# Reciever_Temp.net
KiCad netlist of a schematic drawn in EAGLE
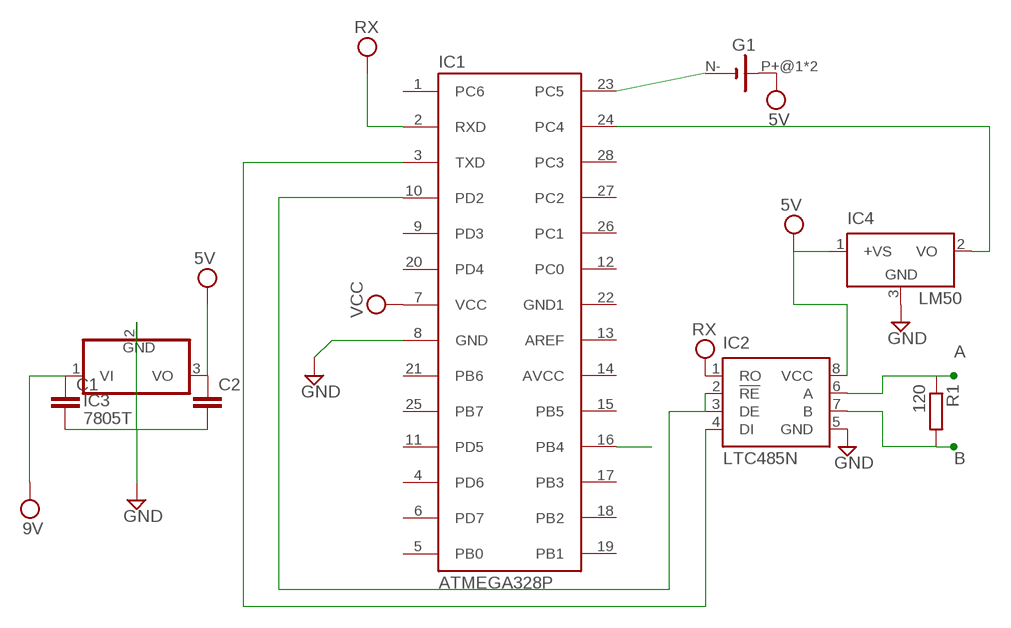
[diagram p0: schematic, sheet 1]

(export (version "E")
  (design (tool "Eeschema 10.0.6"))
  (components
    (comp (ref "C1")
      (value "C-EU050-030X075")
      (footprint "eagle-import:C050-030X075")
      (libsource (lib "eagle-import") (part "C-EU050-030X075"))
    )
    (comp (ref "C2")
      (value "C-EU050-030X075")
      (footprint "eagle-import:C050-030X075")
      (libsource (lib "eagle-import") (part "C-EU050-030X075"))
    )
    (comp (ref "G1")
      (value "BATTERY-HOLDER_11.6MM")
      (footprint "eagle-import:CELL_RETAINER_11.6MM")
      (fields (field (name "MF") "KEYSTONE") (field (name "MPN") "2997"))
      (libsource (lib "eagle-import") (part "BATTERY-HOLDER_11.6MM"))
    )
    (comp (ref "IC1")
      (value "ATMEGA328P")
      (footprint "eagle-import:DIL28-3")
      (libsource (lib "eagle-import") (part "ATMEGA328P"))
    )
    (comp (ref "IC2")
      (value "LTC485N")
      (footprint "eagle-import:DIL08")
      (libsource (lib "eagle-import") (part "LTC485N"))
    )
    (comp (ref "IC3")
      (value "7805T")
      (footprint "eagle-import:TO220H")
      (libsource (lib "eagle-import") (part "78T05"))
    )
    (comp (ref "IC4")
      (value "LM50")
      (footprint "eagle-import:SOT23")
      (libsource (lib "eagle-import") (part "LM50"))
    )
    (comp (ref "R1")
      (value "120")
      (footprint "eagle-import:R0805")
      (libsource (lib "eagle-import") (part "R"))
    )
  )
  (nets
    (net (code "1") (name "/A") (class "Default")
      (node (ref "IC2") (pin "6") (pinfunction "A_6") (pintype "bidirectional"))
      (node (ref "R1") (pin "1") (pinfunction "1_1") (pintype "passive"))
    )
    (net (code "2") (name "/B") (class "Default")
      (node (ref "IC2") (pin "7") (pinfunction "B_7") (pintype "bidirectional"))
      (node (ref "R1") (pin "2") (pinfunction "2_2") (pintype "passive"))
    )
    (net (code "3") (name "/GND1") (class "Default")
      (node (ref "IC1") (pin "22") (pinfunction "GND1_22") (pintype "power_in"))
    )
    (net (code "4") (name "5V") (class "Default")
      (node (ref "C1") (pin "1") (pinfunction "1_1") (pintype "passive"))
      (node (ref "C2") (pin "1") (pinfunction "1_1") (pintype "passive"))
      (node (ref "G1") (pin "P+@1") (pinfunction "+_P+@1") (pintype "passive"))
      (node (ref "G1") (pin "P+@2") (pinfunction "+_P+@2") (pintype "passive"))
      (node (ref "IC1") (pin "2") (pinfunction "RXD_2") (pintype "bidirectional"))
      (node (ref "IC1") (pin "7") (pinfunction "VCC_7") (pintype "power_in"))
      (node (ref "IC2") (pin "1") (pinfunction "RO_1") (pintype "output"))
      (node (ref "IC2") (pin "8") (pinfunction "VCC_8") (pintype "input"))
      (node (ref "IC3") (pin "1") (pinfunction "VI_1") (pintype "input"))
      (node (ref "IC3") (pin "3") (pinfunction "VO_3") (pintype "passive"))
      (node (ref "IC4") (pin "1") (pinfunction "+VS_1") (pintype "input"))
    )
    (net (code "5") (name "GND") (class "Default")
      (node (ref "C1") (pin "2") (pinfunction "2_2") (pintype "passive"))
      (node (ref "C2") (pin "2") (pinfunction "2_2") (pintype "passive"))
      (node (ref "IC1") (pin "8") (pinfunction "GND_8") (pintype "power_in"))
      (node (ref "IC2") (pin "5") (pinfunction "GND_5") (pintype "input"))
      (node (ref "IC3") (pin "2") (pinfunction "GND_2") (pintype "passive"))
      (node (ref "IC4") (pin "3") (pinfunction "GND_3") (pintype "power_in"))
    )
    (net (code "6") (name "Net-(G1--)") (class "Default")
      (node (ref "G1") (pin "N-") (pinfunction "-_N-") (pintype "passive"))
      (node (ref "IC1") (pin "23") (pinfunction "PC5_23") (pintype "bidirectional"))
    )
    (net (code "7") (name "Net-(IC1-PC4)") (class "Default")
      (node (ref "IC1") (pin "24") (pinfunction "PC4_24") (pintype "bidirectional"))
      (node (ref "IC4") (pin "2") (pinfunction "VO_2") (pintype "input"))
    )
    (net (code "8") (name "Net-(IC1-PD2)") (class "Default")
      (node (ref "IC1") (pin "10") (pinfunction "PD2_10") (pintype "bidirectional"))
      (node (ref "IC2") (pin "2") (pinfunction "~{RE}_2") (pintype "input"))
      (node (ref "IC2") (pin "3") (pinfunction "DE_3") (pintype "input"))
    )
    (net (code "9") (name "Net-(IC1-TXD)") (class "Default")
      (node (ref "IC1") (pin "3") (pinfunction "TXD_3") (pintype "bidirectional"))
      (node (ref "IC2") (pin "4") (pinfunction "DI_4") (pintype "input"))
    )
    (net (code "10") (name "unconnected-(IC1-AREF-Pad13)") (class "Default")
      (node (ref "IC1") (pin "13") (pinfunction "AREF_13") (pintype "bidirectional"))
    )
    (net (code "11") (name "unconnected-(IC1-AVCC-Pad14)") (class "Default")
      (node (ref "IC1") (pin "14") (pinfunction "AVCC_14") (pintype "bidirectional"))
    )
    (net (code "12") (name "unconnected-(IC1-PB0-Pad5)") (class "Default")
      (node (ref "IC1") (pin "5") (pinfunction "PB0_5") (pintype "bidirectional"))
    )
    (net (code "13") (name "unconnected-(IC1-PB1-Pad19)") (class "Default")
      (node (ref "IC1") (pin "19") (pinfunction "PB1_19") (pintype "bidirectional"))
    )
    (net (code "14") (name "unconnected-(IC1-PB2-Pad18)") (class "Default")
      (node (ref "IC1") (pin "18") (pinfunction "PB2_18") (pintype "bidirectional"))
    )
    (net (code "15") (name "unconnected-(IC1-PB3-Pad17)") (class "Default")
      (node (ref "IC1") (pin "17") (pinfunction "PB3_17") (pintype "bidirectional"))
    )
    (net (code "16") (name "unconnected-(IC1-PB4-Pad16)") (class "Default")
      (node (ref "IC1") (pin "16") (pinfunction "PB4_16") (pintype "bidirectional"))
    )
    (net (code "17") (name "unconnected-(IC1-PB5-Pad15)") (class "Default")
      (node (ref "IC1") (pin "15") (pinfunction "PB5_15") (pintype "bidirectional"))
    )
    (net (code "18") (name "unconnected-(IC1-PB6-Pad21)") (class "Default")
      (node (ref "IC1") (pin "21") (pinfunction "PB6_21") (pintype "passive"))
    )
    (net (code "19") (name "unconnected-(IC1-PB7-Pad25)") (class "Default")
      (node (ref "IC1") (pin "25") (pinfunction "PB7_25") (pintype "bidirectional"))
    )
    (net (code "20") (name "unconnected-(IC1-PC0-Pad12)") (class "Default")
      (node (ref "IC1") (pin "12") (pinfunction "PC0_12") (pintype "bidirectional"))
    )
    (net (code "21") (name "unconnected-(IC1-PC1-Pad26)") (class "Default")
      (node (ref "IC1") (pin "26") (pinfunction "PC1_26") (pintype "bidirectional"))
    )
    (net (code "22") (name "unconnected-(IC1-PC2-Pad27)") (class "Default")
      (node (ref "IC1") (pin "27") (pinfunction "PC2_27") (pintype "bidirectional"))
    )
    (net (code "23") (name "unconnected-(IC1-PC3-Pad28)") (class "Default")
      (node (ref "IC1") (pin "28") (pinfunction "PC3_28") (pintype "bidirectional"))
    )
    (net (code "24") (name "unconnected-(IC1-PC6-Pad1)") (class "Default")
      (node (ref "IC1") (pin "1") (pinfunction "PC6_1") (pintype "bidirectional"))
    )
    (net (code "25") (name "unconnected-(IC1-PD3-Pad9)") (class "Default")
      (node (ref "IC1") (pin "9") (pinfunction "PD3_9") (pintype "bidirectional"))
    )
    (net (code "26") (name "unconnected-(IC1-PD4-Pad20)") (class "Default")
      (node (ref "IC1") (pin "20") (pinfunction "PD4_20") (pintype "passive"))
    )
    (net (code "27") (name "unconnected-(IC1-PD5-Pad11)") (class "Default")
      (node (ref "IC1") (pin "11") (pinfunction "PD5_11") (pintype "bidirectional"))
    )
    (net (code "28") (name "unconnected-(IC1-PD6-Pad4)") (class "Default")
      (node (ref "IC1") (pin "4") (pinfunction "PD6_4") (pintype "bidirectional"))
    )
    (net (code "29") (name "unconnected-(IC1-PD7-Pad6)") (class "Default")
      (node (ref "IC1") (pin "6") (pinfunction "PD7_6") (pintype "bidirectional"))
    )
  )
)
